# CAN.net
KiCad netlist of a schematic drawn in Altium Designer
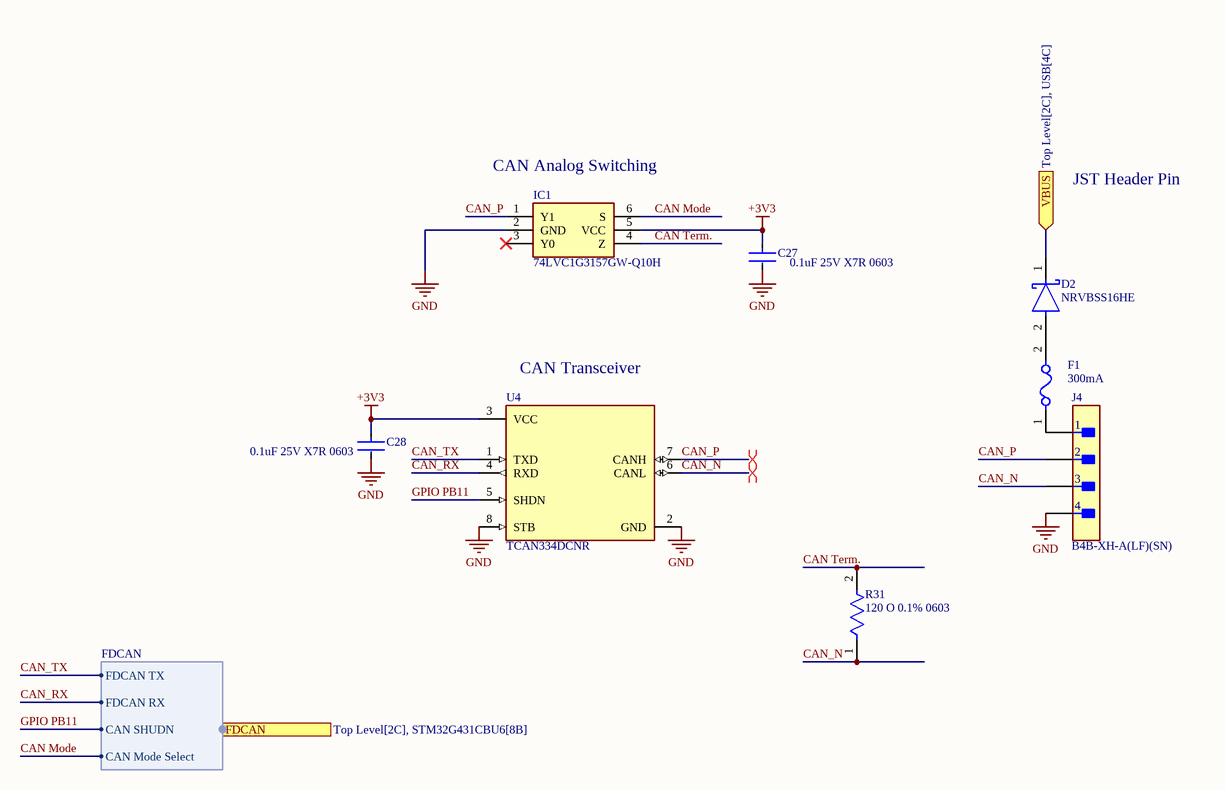
[diagram p0: CAN.SchDoc]

(export (version "E")
  (design (tool "Eeschema 10.0.6"))
  (components
    (comp (ref "C27")
      (value "0.1uF 25V X7R 0603")
      (footprint "FP-C0603C-CF-MFG")
      (description "CAP CER 0.1UF 25V X7R 0603")
      (fields (field (name "TOLERANCE") "0.1") (field (name "MANUFACTURER PART NUMBER") "C0603C104K3RACAUTO"))
      (libsource (lib "Altium Content Vault") (part "b4654b650e69147ec39a6b967a45e02"))
    )
    (comp (ref "C28")
      (value "0.1uF 25V X7R 0603")
      (footprint "FP-C0603C-CF-MFG")
      (description "CAP CER 0.1UF 25V X7R 0603")
      (fields (field (name "TOLERANCE") "0.1") (field (name "MANUFACTURER PART NUMBER") "C0603C104K3RACAUTO"))
      (libsource (lib "Altium Content Vault") (part "b4654b650e69147ec39a6b967a45e02"))
    )
    (comp (ref "D2")
      (value "NRVBSS16HE")
      (footprint "FP-477AD-MFG")
      (description "NRVBSS16HE Rectifier Diode, Schottky, 1 Phase, 1 Element, 1A, 60V V(RRM), Silicon")
      (libsource (lib "Altium Content Vault") (part "c1678fac7984e62e0809fbf79c06691"))
    )
    (comp (ref "F1")
      (value "300mA")
      (footprint "FP-0805L010-MFG")
      (libsource (lib "Altium Content Vault") (part "5bcf9b9f640e542cf0359d10258e979"))
    )
    (comp (ref "IC1")
      (value "74LVC1G3157GW-Q10H")
      (footprint "SOP80P1176X120-54N:SOT65P210X110-6N")
      (description "Integrated Circuit")
      (fields (field (name "MOUSER PART NUMBER") "771-74LVC1G3157GWQ10"))
      (libsource (lib "*") (part "74LVC1G3157GW-Q10H"))
    )
    (comp (ref "J4")
      (value "B4B-XH-A(LF)(SN)")
      (footprint "FP-B4B-XH-A_LF_SN-MFG")
      (description "CONN HEADER VERT 4POS 2.5MM")
      (libsource (lib "Altium Content Vault") (part "299a8cea1bdcbc3624fe62c390fa72c"))
    )
    (comp (ref "R31")
      (value "120 O 0.1% 0603")
      (footprint "FP-RT0603-MFG")
      (description "RES SMD 120 OHM 0.1% 1/10W 0603")
      (fields
        (field (name "MANUFACTURER PART NUMBER") "RT0603BRC07120RL")
        (field (name "MANUFACTURER") "Yageo")
      )
      (libsource (lib "Altium Content Vault") (part "1029c3af85768c4190bb7ad29bc67b5"))
    )
    (comp (ref "U4")
      (value "TCAN334DCNR")
      (footprint "FP-DCN0008A-IPC_C")
      (description "IC TRANSCEIVER 1/1 SOT23-8")
      (libsource (lib "Altium Content Vault") (part "f6c6e5888f7035d3f7adb2c43587ba1"))
    )
  )
  (nets
    (net (code "2") (name "+3V3") (class "Default")
      (node (ref "C27") (pin "1") (pinfunction "1_1") (pintype "passive"))
      (node (ref "C28") (pin "1") (pinfunction "1_1") (pintype "passive"))
      (node (ref "IC1") (pin "5") (pinfunction "VCC_5") (pintype "passive"))
      (node (ref "U4") (pin "3") (pinfunction "VCC_3") (pintype "power_in"))
    )
    (net (code "3") (name "/CAN Mode") (class "Default")
      (node (ref "IC1") (pin "6") (pinfunction "S_6") (pintype "passive"))
    )
    (net (code "4") (name "/CAN Term.") (class "Default")
      (node (ref "IC1") (pin "4") (pinfunction "Z_4") (pintype "passive"))
      (node (ref "R31") (pin "2") (pinfunction "2_2") (pintype "passive"))
    )
    (net (code "5") (name "/CAN_N") (class "Default")
      (node (ref "J4") (pin "3") (pinfunction "3_3") (pintype "passive"))
      (node (ref "R31") (pin "1") (pinfunction "1_1") (pintype "passive"))
      (node (ref "U4") (pin "6") (pinfunction "CANL_6") (pintype "bidirectional"))
    )
    (net (code "6") (name "/CAN_P") (class "Default")
      (node (ref "IC1") (pin "1") (pinfunction "Y1_1") (pintype "passive"))
      (node (ref "J4") (pin "2") (pinfunction "2_2") (pintype "passive"))
      (node (ref "U4") (pin "7") (pinfunction "CANH_7") (pintype "bidirectional"))
    )
    (net (code "7") (name "/CAN_RX") (class "Default")
      (node (ref "U4") (pin "4") (pinfunction "RXD_4") (pintype "output"))
    )
    (net (code "8") (name "/CAN_TX") (class "Default")
      (node (ref "U4") (pin "1") (pinfunction "TXD_1") (pintype "input"))
    )
    (net (code "9") (name "/GPIO PB11") (class "Default")
      (node (ref "U4") (pin "5") (pinfunction "SHDN_5") (pintype "input"))
    )
    (net (code "10") (name "/VBUS") (class "Default")
      (node (ref "D2") (pin "1") (pinfunction "C_1") (pintype "passive"))
    )
    (net (code "12") (name "GND") (class "Default")
      (node (ref "C27") (pin "2") (pinfunction "2_2") (pintype "passive"))
      (node (ref "C28") (pin "2") (pinfunction "2_2") (pintype "passive"))
      (node (ref "IC1") (pin "2") (pinfunction "GND_2") (pintype "passive"))
      (node (ref "J4") (pin "4") (pinfunction "4_4") (pintype "passive"))
      (node (ref "U4") (pin "2") (pinfunction "GND_2") (pintype "power_in"))
      (node (ref "U4") (pin "8") (pinfunction "STB_8") (pintype "input"))
    )
    (net (code "13") (name "Net-(D2-A)") (class "Default")
      (node (ref "D2") (pin "2") (pinfunction "A_2") (pintype "passive"))
      (node (ref "F1") (pin "2") (pinfunction "2_2") (pintype "passive"))
    )
    (net (code "14") (name "Net-(F1-Pad1)") (class "Default")
      (node (ref "F1") (pin "1") (pinfunction "1_1") (pintype "passive"))
      (node (ref "J4") (pin "1") (pinfunction "1_1") (pintype "passive"))
    )
    (net (code "15") (name "unconnected-(IC1-Y0-Pad3)") (class "Default")
      (node (ref "IC1") (pin "3") (pinfunction "Y0_3") (pintype "passive+no_connect"))
    )
  )
)
